# 8-Bluetooth.net
KiCad netlist of a schematic drawn in Altium Designer
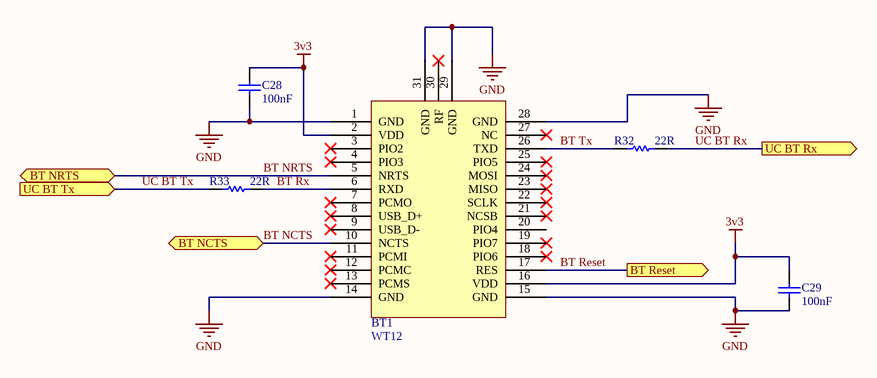
[diagram p0: 8-Bluetooth.SchDoc]

(export (version "E")
  (design (tool "Eeschema 10.0.6"))
  (components
    (comp (ref "BT1") (value "WT12") (footprint "WT12") (libsource (lib "VCU Library") (part "WT12")))
    (comp (ref "C28")
      (value "100nF")
      (footprint "1608[0603]")
      (description "Capacitor")
      (fields
        (field (name "MANUFACTURER") "Yageo")
        (field (name "MANUFACTURER PART NUMBER") "CC0603KRX7R9BB104")
      )
      (libsource (lib "Miscellaneous Devices") (part "Cap"))
    )
    (comp (ref "C29")
      (value "100nF")
      (footprint "1608[0603]")
      (description "Capacitor")
      (fields
        (field (name "MANUFACTURER") "Yageo")
        (field (name "MANUFACTURER PART NUMBER") "CC0603KRX7R9BB104")
      )
      (libsource (lib "Miscellaneous Devices") (part "Cap"))
    )
    (comp (ref "R32")
      (value "22R")
      (footprint "1608[0603]")
      (description "Resistor")
      (fields
        (field (name "MANUFACTURER") "Yageo")
        (field (name "MANUFACTURER PART NUMBER") "RC0603JR-0722RL")
      )
      (libsource (lib "Miscellaneous Devices") (part "Res1"))
    )
    (comp (ref "R33")
      (value "22R")
      (footprint "1608[0603]")
      (description "Resistor")
      (fields
        (field (name "MANUFACTURER") "Yageo")
        (field (name "MANUFACTURER PART NUMBER") "RC0603JR-0722RL")
      )
      (libsource (lib "Miscellaneous Devices") (part "Res1"))
    )
  )
  (nets
    (net (code "1") (name "/BT NCTS") (class "Default")
      (node (ref "BT1") (pin "10") (pinfunction "NCTS_10") (pintype "passive"))
    )
    (net (code "2") (name "/BT NRTS") (class "Default")
      (node (ref "BT1") (pin "5") (pinfunction "NRTS_5") (pintype "passive"))
    )
    (net (code "3") (name "/BT Reset") (class "Default")
      (node (ref "BT1") (pin "17") (pinfunction "RES_17") (pintype "passive"))
    )
    (net (code "4") (name "/BT Rx") (class "Default")
      (node (ref "BT1") (pin "6") (pinfunction "RXD_6") (pintype "passive"))
      (node (ref "R33") (pin "2") (pinfunction "2_2") (pintype "passive"))
    )
    (net (code "5") (name "/BT Tx") (class "Default")
      (node (ref "BT1") (pin "26") (pinfunction "TXD_26") (pintype "passive"))
      (node (ref "R32") (pin "1") (pinfunction "1_1") (pintype "passive"))
    )
    (net (code "6") (name "/UC BT Rx") (class "Default")
      (node (ref "R32") (pin "2") (pinfunction "2_2") (pintype "passive"))
    )
    (net (code "7") (name "/UC BT Tx") (class "Default")
      (node (ref "R33") (pin "1") (pinfunction "1_1") (pintype "passive"))
    )
    (net (code "8") (name "3v3") (class "Default")
      (node (ref "BT1") (pin "16") (pinfunction "VDD_16") (pintype "passive"))
      (node (ref "BT1") (pin "2") (pinfunction "VDD_2") (pintype "passive"))
      (node (ref "C28") (pin "2") (pinfunction "2_2") (pintype "passive"))
      (node (ref "C29") (pin "2") (pinfunction "2_2") (pintype "passive"))
    )
    (net (code "9") (name "GND") (class "Default")
      (node (ref "BT1") (pin "1") (pinfunction "GND_1") (pintype "passive"))
      (node (ref "BT1") (pin "14") (pinfunction "GND_14") (pintype "passive"))
      (node (ref "BT1") (pin "15") (pinfunction "GND_15") (pintype "passive"))
      (node (ref "BT1") (pin "28") (pinfunction "GND_28") (pintype "passive"))
      (node (ref "BT1") (pin "29") (pinfunction "GND_29") (pintype "passive"))
      (node (ref "BT1") (pin "31") (pinfunction "GND_31") (pintype "passive"))
      (node (ref "C28") (pin "1") (pinfunction "1_1") (pintype "passive"))
      (node (ref "C29") (pin "1") (pinfunction "1_1") (pintype "passive"))
    )
    (net (code "10") (name "unconnected-(BT1-MISO-Pad23)") (class "Default")
      (node (ref "BT1") (pin "23") (pinfunction "MISO_23") (pintype "passive+no_connect"))
    )
    (net (code "11") (name "unconnected-(BT1-MOSI-Pad24)") (class "Default")
      (node (ref "BT1") (pin "24") (pinfunction "MOSI_24") (pintype "passive+no_connect"))
    )
    (net (code "12") (name "unconnected-(BT1-NC-Pad27)") (class "Default")
      (node (ref "BT1") (pin "27") (pinfunction "NC_27") (pintype "passive+no_connect"))
    )
    (net (code "13") (name "unconnected-(BT1-NCSB-Pad21)") (class "Default")
      (node (ref "BT1") (pin "21") (pinfunction "NCSB_21") (pintype "passive+no_connect"))
    )
    (net (code "14") (name "unconnected-(BT1-PCMC-Pad12)") (class "Default")
      (node (ref "BT1") (pin "12") (pinfunction "PCMC_12") (pintype "passive+no_connect"))
    )
    (net (code "15") (name "unconnected-(BT1-PCMI-Pad11)") (class "Default")
      (node (ref "BT1") (pin "11") (pinfunction "PCMI_11") (pintype "passive+no_connect"))
    )
    (net (code "16") (name "unconnected-(BT1-PCMO-Pad7)") (class "Default")
      (node (ref "BT1") (pin "7") (pinfunction "PCMO_7") (pintype "passive+no_connect"))
    )
    (net (code "17") (name "unconnected-(BT1-PCMS-Pad13)") (class "Default")
      (node (ref "BT1") (pin "13") (pinfunction "PCMS_13") (pintype "passive+no_connect"))
    )
    (net (code "18") (name "unconnected-(BT1-PIO2-Pad3)") (class "Default")
      (node (ref "BT1") (pin "3") (pinfunction "PIO2_3") (pintype "passive+no_connect"))
    )
    (net (code "19") (name "unconnected-(BT1-PIO3-Pad4)") (class "Default")
      (node (ref "BT1") (pin "4") (pinfunction "PIO3_4") (pintype "passive+no_connect"))
    )
    (net (code "20") (name "unconnected-(BT1-PIO4-Pad20)") (class "Default")
      (node (ref "BT1") (pin "20") (pinfunction "PIO4_20") (pintype "passive"))
    )
    (net (code "21") (name "unconnected-(BT1-PIO5-Pad25)") (class "Default")
      (node (ref "BT1") (pin "25") (pinfunction "PIO5_25") (pintype "passive+no_connect"))
    )
    (net (code "22") (name "unconnected-(BT1-PIO6-Pad18)") (class "Default")
      (node (ref "BT1") (pin "18") (pinfunction "PIO6_18") (pintype "passive+no_connect"))
    )
    (net (code "23") (name "unconnected-(BT1-PIO7-Pad19)") (class "Default")
      (node (ref "BT1") (pin "19") (pinfunction "PIO7_19") (pintype "passive+no_connect"))
    )
    (net (code "24") (name "unconnected-(BT1-RF-Pad30)") (class "Default")
      (node (ref "BT1") (pin "30") (pinfunction "RF_30") (pintype "passive+no_connect"))
    )
    (net (code "25") (name "unconnected-(BT1-SCLK-Pad22)") (class "Default")
      (node (ref "BT1") (pin "22") (pinfunction "SCLK_22") (pintype "passive+no_connect"))
    )
    (net (code "26") (name "unconnected-(BT1-USB_D+-Pad8)") (class "Default")
      (node (ref "BT1") (pin "8") (pinfunction "USB_D+_8") (pintype "passive+no_connect"))
    )
    (net (code "27") (name "unconnected-(BT1-USB_D--Pad9)") (class "Default")
      (node (ref "BT1") (pin "9") (pinfunction "USB_D-_9") (pintype "passive+no_connect"))
    )
  )
)
